# Touch.net
KiCad netlist of a schematic drawn in Altium Designer
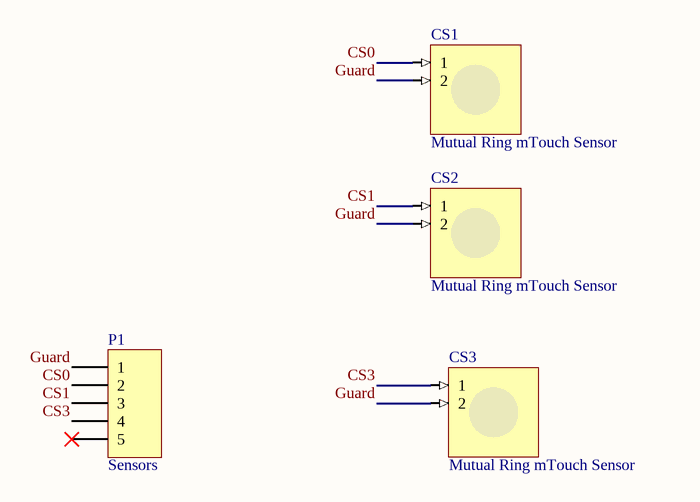
[diagram p0: Touch.SchDoc]

(export (version "E")
  (design (tool "Eeschema 10.0.6"))
  (components
    (comp (ref "CS1")
      (value "Mutual Ring mTouch Sensor")
      (libsource (lib "Microchip mTouch") (part "mTouchMutualRingSensor"))
    )
    (comp (ref "CS2")
      (value "Mutual Ring mTouch Sensor")
      (libsource (lib "Microchip mTouch") (part "mTouchMutualRingSensor"))
    )
    (comp (ref "CS3")
      (value "Mutual Ring mTouch Sensor")
      (libsource (lib "Microchip mTouch") (part "mTouchMutualRingSensor"))
    )
    (comp (ref "P1")
      (value "Sensors")
      (footprint "HDR1X5")
      (description "Header, 5-Pin")
      (fields (field (name "PUBLISHER") "Altium Limited"))
      (libsource (lib "Miscellaneous Connectors") (part "Header 5"))
    )
  )
  (nets
    (net (code "1") (name "/CS0") (class "Default")
      (node (ref "CS1") (pin "1") (pinfunction "1_1") (pintype "input"))
      (node (ref "P1") (pin "2") (pinfunction "2_2") (pintype "passive"))
    )
    (net (code "2") (name "/CS1") (class "Default")
      (node (ref "CS2") (pin "1") (pinfunction "1_1") (pintype "input"))
      (node (ref "P1") (pin "3") (pinfunction "3_3") (pintype "passive"))
    )
    (net (code "3") (name "/CS3") (class "Default")
      (node (ref "CS3") (pin "1") (pinfunction "1_1") (pintype "input"))
      (node (ref "P1") (pin "4") (pinfunction "4_4") (pintype "passive"))
    )
    (net (code "4") (name "/Guard") (class "Default")
      (node (ref "CS1") (pin "2") (pinfunction "2_2") (pintype "input"))
      (node (ref "CS2") (pin "2") (pinfunction "2_2") (pintype "input"))
      (node (ref "CS3") (pin "2") (pinfunction "2_2") (pintype "input"))
      (node (ref "P1") (pin "1") (pinfunction "1_1") (pintype "passive"))
    )
    (net (code "5") (name "unconnected-(P1-Pad5)") (class "Default")
      (node (ref "P1") (pin "5") (pinfunction "5_5") (pintype "passive+no_connect"))
    )
  )
)
